# A2_Full_Schematic.net
KiCad netlist of a schematic drawn in Altium Designer
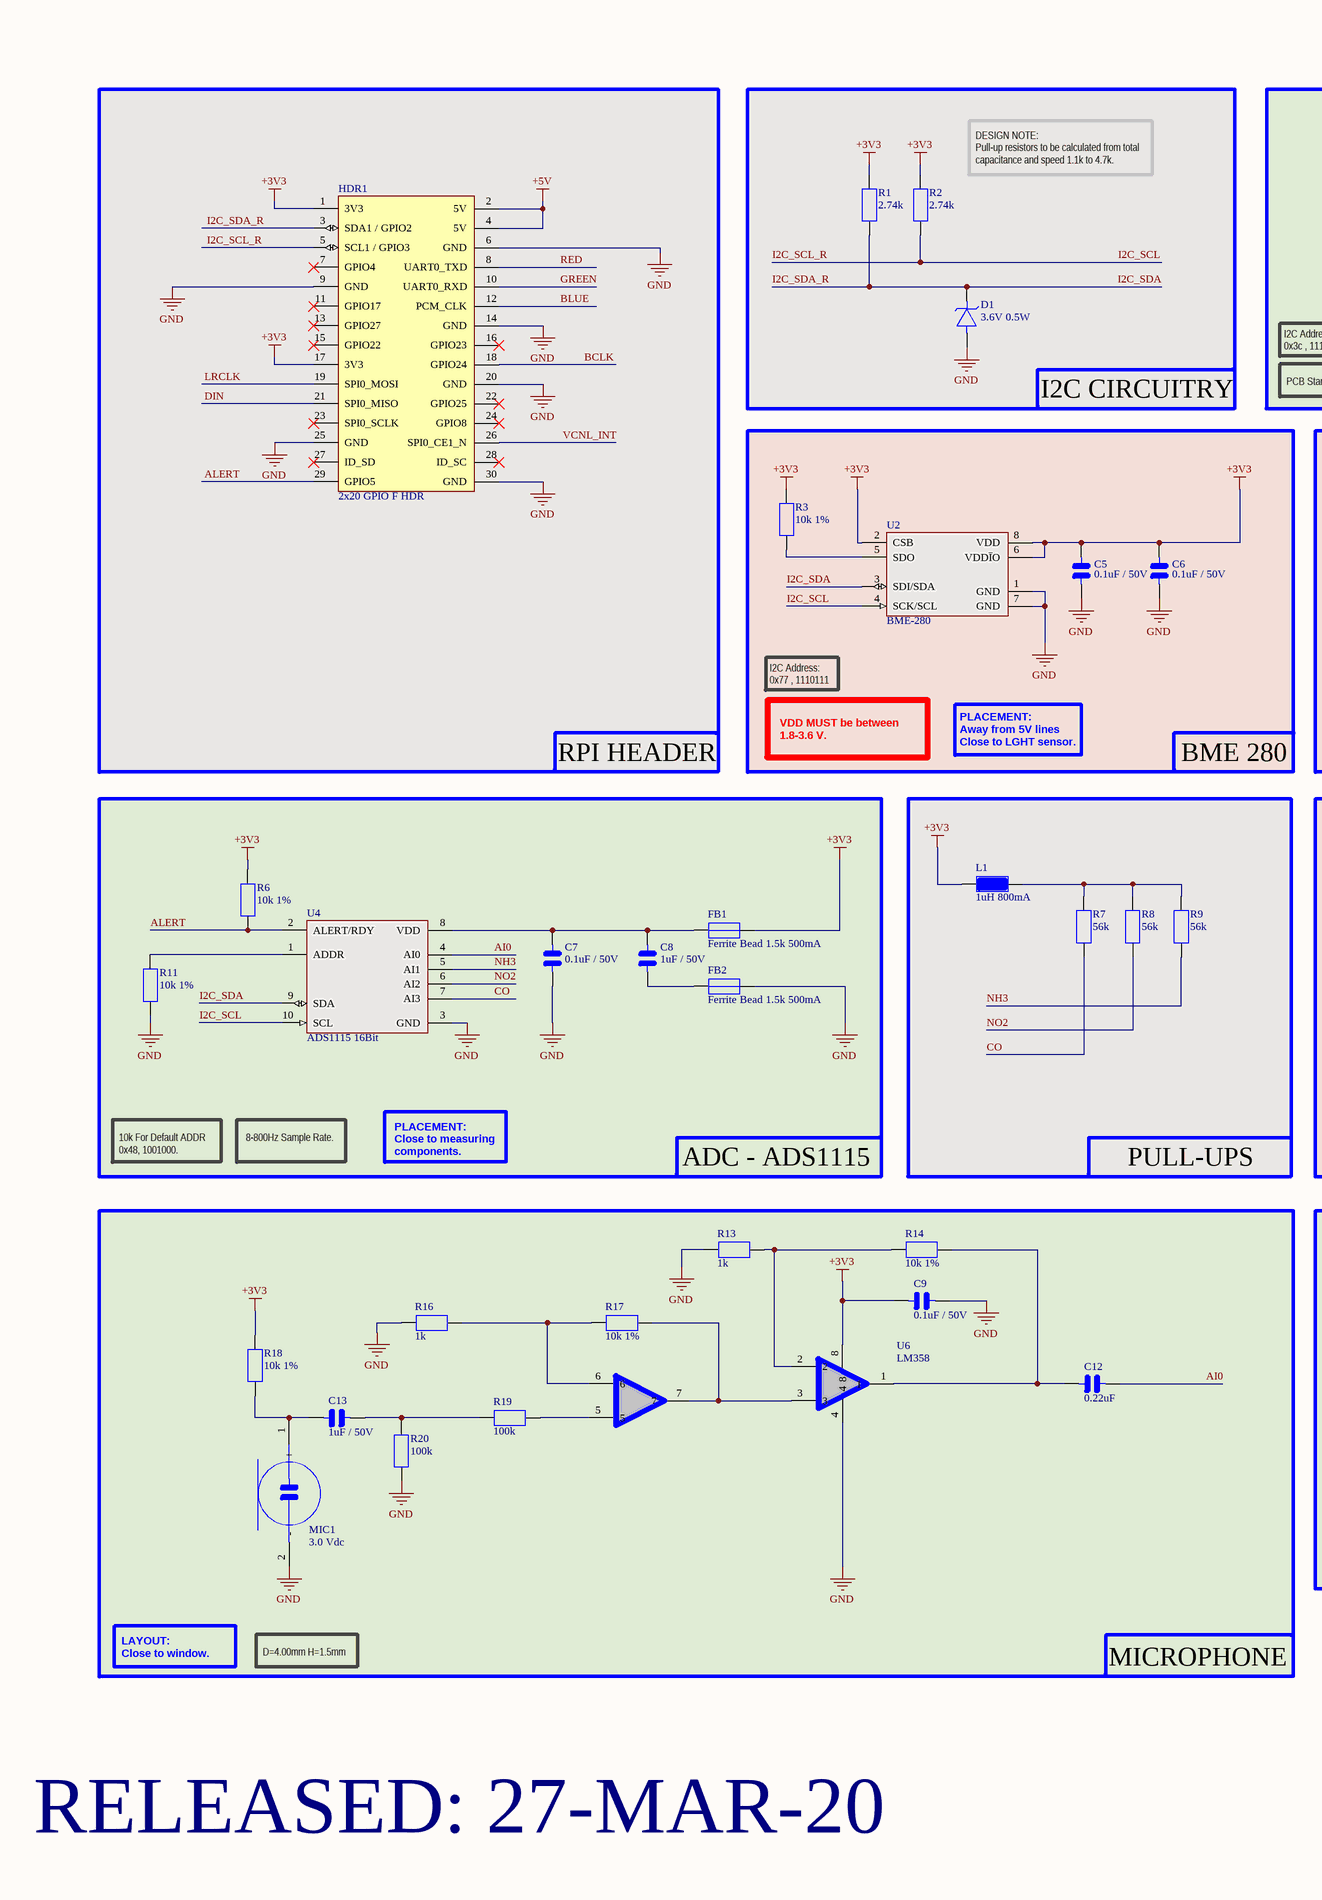
[diagram p0: A2_Full_Schematic.SchDoc, left]
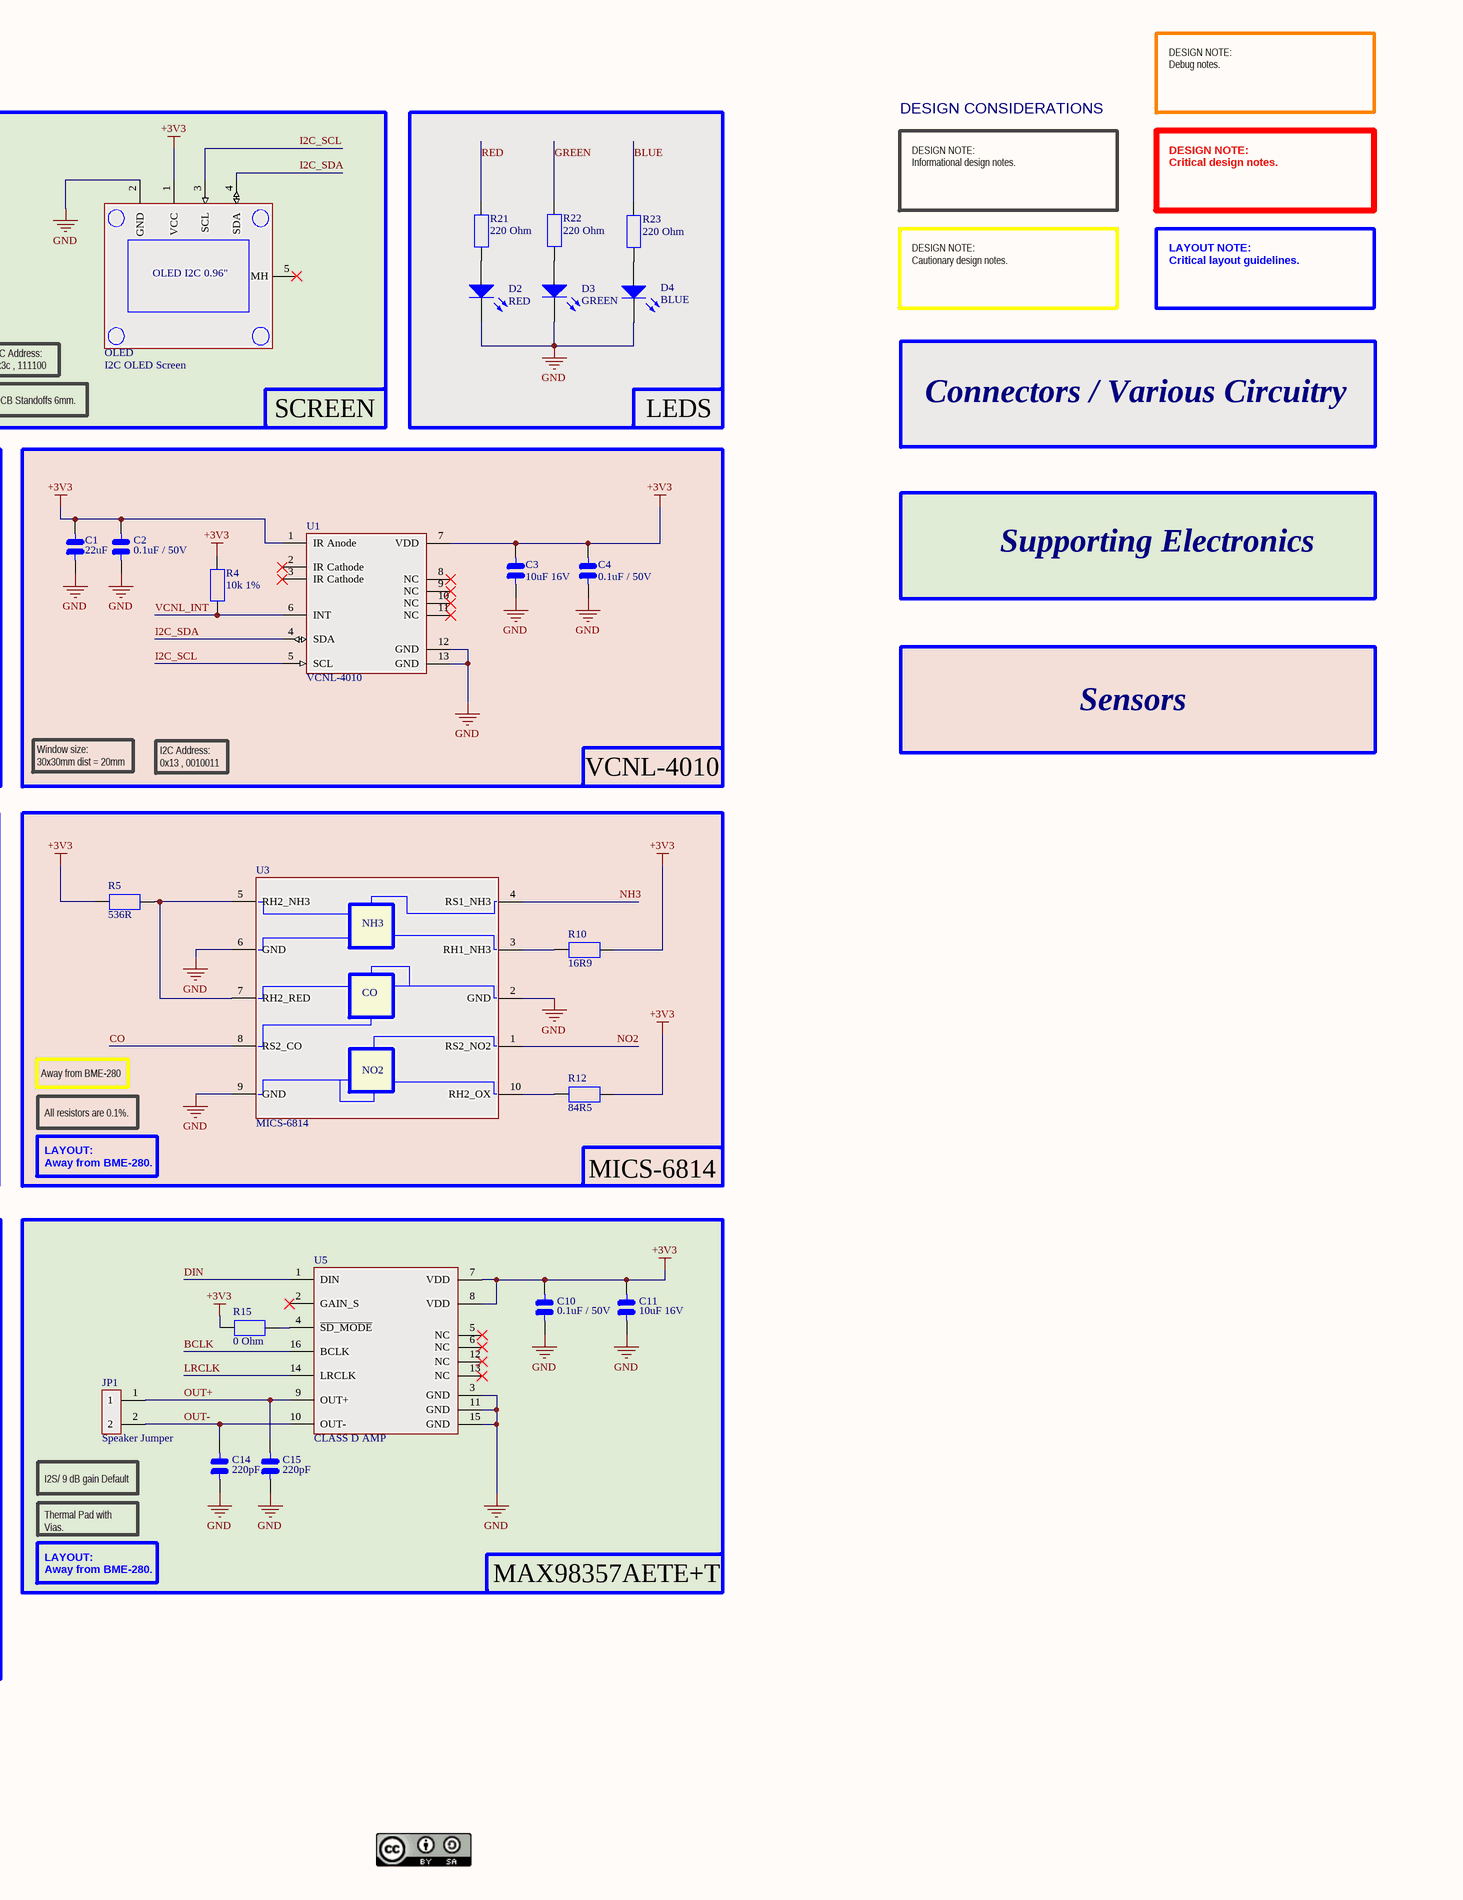
[diagram p1: A2_Full_Schematic.SchDoc, right]

(export (version "E")
  (design (tool "Eeschema 10.0.6"))
  (components
    (comp (ref "C1")
      (value "22uF")
      (footprint "C0805")
      (description "CAP CER 22UF 10V JB 0805")
      (fields (field (name "TOLERANCE") "20%"))
      (libsource (lib "Parts_Lib_SMAQ") (part "C2012JB1A226M085AC"))
    )
    (comp (ref "C2")
      (value "0.1uF / 50V")
      (footprint "C0805")
      (description "CAP CER 0.1UF 50V X7R 0805")
      (fields (field (name "TOLERANCE") "5%"))
      (libsource (lib "Parts_Lib_SMAQ") (part "08055C104JAT4A"))
    )
    (comp (ref "C3")
      (value "10uF 16V")
      (footprint "C0805")
      (libsource (lib "Parts_Lib_SMAQ") (part "0805YC106MAT2A"))
    )
    (comp (ref "C4")
      (value "0.1uF / 50V")
      (footprint "C0805")
      (description "CAP CER 0.1UF 50V X7R 0805")
      (fields (field (name "TOLERANCE") "5%"))
      (libsource (lib "") (part "08055C104JAT4A_2"))
    )
    (comp (ref "C5")
      (value "0.1uF / 50V")
      (footprint "C0805")
      (description "CAP CER 0.1UF 50V X7R 0805")
      (fields (field (name "TOLERANCE") "5%"))
      (libsource (lib "") (part "08055C104JAT4A_1"))
    )
    (comp (ref "C6")
      (value "0.1uF / 50V")
      (footprint "C0805")
      (description "CAP CER 0.1UF 50V X7R 0805")
      (fields (field (name "TOLERANCE") "5%"))
      (libsource (lib "") (part "08055C104JAT4A_1"))
    )
    (comp (ref "C7")
      (value "0.1uF / 50V")
      (footprint "C0805")
      (description "CAP CER 0.1UF 50V X7R 0805")
      (fields (field (name "TOLERANCE") "5%"))
      (libsource (lib "") (part "08055C104JAT4A_1"))
    )
    (comp (ref "C8")
      (value "1uF / 50V")
      (footprint "C0805")
      (fields (field (name "TOLERANCE") "5%") (field (name "VOLTAGE") "50V"))
      (libsource (lib "Parts_Lib_SMAQ") (part "08055C105JAT2A"))
    )
    (comp (ref "C9")
      (value "0.1uF / 50V")
      (footprint "C0805")
      (description "CAP CER 0.1UF 50V X7R 0805")
      (fields (field (name "TOLERANCE") "5%"))
      (libsource (lib "") (part "08055C104JAT4A_3"))
    )
    (comp (ref "C10")
      (value "0.1uF / 50V")
      (footprint "C0805")
      (description "CAP CER 0.1UF 50V X7R 0805")
      (fields (field (name "TOLERANCE") "5%"))
      (libsource (lib "Parts_Lib_SMAQ") (part "08055C104JAT4A"))
    )
    (comp (ref "C11")
      (value "10uF 16V")
      (footprint "C0805")
      (libsource (lib "Parts_Lib_SMAQ") (part "0805YC106MAT2A"))
    )
    (comp (ref "C12")
      (value "0.22uF")
      (footprint "C0805")
      (description "Multilayer Ceramic Capacitors MLCC - SMD/SMT 25V 0.22uF X7R 0805 5% AEC-Q200")
      (libsource (lib "Parts_Lib_SMAQ") (part "08053C224J4Z2A"))
    )
    (comp (ref "C13")
      (value "1uF / 50V")
      (footprint "C0805")
      (fields (field (name "TOLERANCE") "5%") (field (name "VOLTAGE") "50V"))
      (libsource (lib "") (part "08055C105JAT2A_1"))
    )
    (comp (ref "C14")
      (value "220pF")
      (footprint "C0805")
      (description "T&R / COMMERCIAL CHIP")
      (fields (field (name "TOLERANCE") "1%"))
      (libsource (lib "Parts_Lib_SMAQ") (part "08055A221F4T2A"))
    )
    (comp (ref "C15")
      (value "220pF")
      (footprint "C0805")
      (description "T&R / COMMERCIAL CHIP")
      (fields (field (name "TOLERANCE") "1%"))
      (libsource (lib "Parts_Lib_SMAQ") (part "08055A221F4T2A"))
    )
    (comp (ref "D1")
      (value "3.6V 0.5W")
      (footprint "SOD-123")
      (description "Diode Zener Single 3.6V 2% 500mW 2-Pin SOD-123 T/R")
      (fields (field (name "TOLERANCE") "2%"))
      (libsource (lib "Parts_Lib_SMAQ") (part "BZT52B3V6-E3-08"))
    )
    (comp (ref "D2")
      (value "RED")
      (footprint "LED-1")
      (description "Typical RED GaAs LED")
      (fields (field (name "PUBLISHER") "Altium Limited"))
      (libsource (lib "Miscellaneous Devices") (part "LED1"))
    )
    (comp (ref "D3")
      (value "GREEN")
      (footprint "LED-1")
      (description "Typical RED GaAs LED")
      (fields (field (name "PUBLISHER") "Altium Limited"))
      (libsource (lib "Miscellaneous Devices") (part "LED1"))
    )
    (comp (ref "D4")
      (value "BLUE")
      (footprint "LED-1")
      (description "Typical RED GaAs LED")
      (fields (field (name "PUBLISHER") "Altium Limited"))
      (libsource (lib "Miscellaneous Devices") (part "LED1"))
    )
    (comp (ref "FB1")
      (value "Ferrite Bead 1.5k 500mA")
      (footprint "C0805")
      (description "Ferrite Beads Multi-Layer 1.5KOhm 25% 100MHz 500mA 400mOhm DCR 0805")
      (fields (field (name "TOLERANCE") "25%"))
      (libsource (lib "Parts_Lib_SMAQ") (part "MMZ2012Y152B"))
    )
    (comp (ref "FB2")
      (value "Ferrite Bead 1.5k 500mA")
      (footprint "C0805")
      (description "Ferrite Beads Multi-Layer 1.5KOhm 25% 100MHz 500mA 400mOhm DCR 0805")
      (fields (field (name "TOLERANCE") "25%"))
      (libsource (lib "Parts_Lib_SMAQ") (part "MMZ2012Y152B"))
    )
    (comp (ref "HDR1")
      (value "2x20 GPIO F HDR")
      (footprint "2x20_Pi_Header")
      (description "GPIO FEMALE HEADER RASPBERRY PI")
      (libsource (lib "Parts_Lib_SMAQ") (part "2X20 Female Header"))
    )
    (comp (ref "JP1")
      (value "Speaker Jumper")
      (footprint "Speaker Jumper")
      (libsource (lib "Parts_Lib_SMAQ") (part "Speaker Jumper"))
    )
    (comp (ref "L1")
      (value "1uH 800mA")
      (footprint "C0805")
      (description "FIXED IND 1UH 800MA 130 MOHM SMD")
      (libsource (lib "Parts_Lib_SMAQ") (part "KLZ2012MHR1R0HTD25"))
    )
    (comp (ref "MIC1")
      (value "3.0 Vdc")
      (footprint "Speaker Jumper")
      (description "4.0 mm, Omnidirectional, Wire Leads, 3.0 Vdc, IP65 Rated, Electret Condenser Microphone")
      (libsource (lib "Parts_Lib_SMAQ") (part "CMC-4015-25L100"))
    )
    (comp (ref "OLED")
      (value "I2C OLED Screen")
      (footprint "OLED_I2C_0.96\"")
      (libsource (lib "Parts_Lib_SMAQ") (part "OLED_I2C_BREAKOUT"))
    )
    (comp (ref "R1")
      (value "2.74k")
      (footprint "R0805 (2012M)")
      (description "Surface Mount Chip Resistor, Thin Film, AEC-Q200 ERA Series, 2.74 kohm, 125 mW, 0.1%, 100 V")
      (fields (field (name "TOLERANCE") "0.1%"))
      (libsource (lib "Parts_Lib_SMAQ") (part "ERA-6AEB2741V"))
    )
    (comp (ref "R2")
      (value "2.74k")
      (footprint "R0805 (2012M)")
      (description "Surface Mount Chip Resistor, Thin Film, AEC-Q200 ERA Series, 2.74 kohm, 125 mW, 0.1%, 100 V")
      (fields (field (name "TOLERANCE") "0.1%"))
      (libsource (lib "Parts_Lib_SMAQ") (part "ERA-6AEB2741V"))
    )
    (comp (ref "R3")
      (value "10k 1%")
      (footprint "R0805 (2012M)")
      (description "RES SMD 10K OHM 1% 1/8W 0805")
      (fields (field (name "TOLERANCE") "1%"))
      (libsource (lib "Parts_Lib_SMAQ") (part "AT0805FRE0710KL"))
    )
    (comp (ref "R4")
      (value "10k 1%")
      (footprint "R0805 (2012M)")
      (description "RES SMD 10K OHM 1% 1/8W 0805")
      (fields (field (name "TOLERANCE") "1%"))
      (libsource (lib "Parts_Lib_SMAQ") (part "AT0805FRE0710KL"))
    )
    (comp (ref "R5")
      (value "536R")
      (footprint "R0805 (2012M)")
      (description "RES SMD 536 OHM 0.1% 1/8W 0805")
      (fields (field (name "TOLERANCE") "0.1%"))
      (libsource (lib "Parts_Lib_SMAQ") (part "ERA6AEB5360V"))
    )
    (comp (ref "R6")
      (value "10k 1%")
      (footprint "R0805 (2012M)")
      (description "RES SMD 10K OHM 1% 1/8W 0805")
      (fields (field (name "TOLERANCE") "1%"))
      (libsource (lib "Parts_Lib_SMAQ") (part "AT0805FRE0710KL"))
    )
    (comp (ref "R7")
      (value "56k")
      (footprint "R0805 (2012M)")
      (description "RES SMD 56K OHM 0.1% 1/8W 0805")
      (fields (field (name "TOLERANCE") "0.1%"))
      (libsource (lib "Parts_Lib_SMAQ") (part "ERA-6AEB563V"))
    )
    (comp (ref "R8")
      (value "56k")
      (footprint "R0805 (2012M)")
      (description "RES SMD 56K OHM 0.1% 1/8W 0805")
      (fields (field (name "TOLERANCE") "0.1%"))
      (libsource (lib "Parts_Lib_SMAQ") (part "ERA-6AEB563V"))
    )
    (comp (ref "R9")
      (value "56k")
      (footprint "R0805 (2012M)")
      (description "RES SMD 56K OHM 0.1% 1/8W 0805")
      (fields (field (name "TOLERANCE") "0.1%"))
      (libsource (lib "Parts_Lib_SMAQ") (part "ERA-6AEB563V"))
    )
    (comp (ref "R10")
      (value "16R9")
      (footprint "R0805 (2012M)")
      (description "Res Thick Film 0805 16.9 Ohm 1% 1/4W 300ppm/C Molded SMD Punched Carrier T/R")
      (fields (field (name "TOLERANCE") "1%"))
      (libsource (lib "Parts_Lib_SMAQ") (part "ERJ-P06F17R4V"))
    )
    (comp (ref "R11")
      (value "10k 1%")
      (footprint "R0805 (2012M)")
      (description "RES SMD 10K OHM 1% 1/8W 0805")
      (fields (field (name "TOLERANCE") "1%"))
      (libsource (lib "Parts_Lib_SMAQ") (part "AT0805FRE0710KL"))
    )
    (comp (ref "R12")
      (value "84R5")
      (footprint "R0805 (2012M)")
      (description "RES SMD 84.5 OHM 0.1% 1/8W 0805")
      (fields (field (name "TOLERANCE") "0.1%"))
      (libsource (lib "Parts_Lib_SMAQ") (part "ERA-6AEB84R5V"))
    )
    (comp (ref "R13")
      (value "1k")
      (footprint "R0805 (2012M)")
      (description "Res Thin Film 0805 1K Ohm 0.5% 1/8W ±25ppm/°C Molded SMD SMD Punched Carrier T/R")
      (fields (field (name "TOLERANCE") "0.5%"))
      (libsource (lib "Parts_Lib_SMAQ") (part "ERA-6AED102V"))
    )
    (comp (ref "R14")
      (value "10k 1%")
      (footprint "R0805 (2012M)")
      (description "RES SMD 10K OHM 1% 1/8W 0805")
      (fields (field (name "TOLERANCE") "1%"))
      (libsource (lib "Parts_Lib_SMAQ") (part "AT0805FRE0710KL"))
    )
    (comp (ref "R15")
      (value "0 Ohm")
      (footprint "R0805 (2012M)")
      (description "RES SMD 0 OHM JUMPER 1/8W 0805")
      (fields (field (name "TOLERANCE") "5%"))
      (libsource (lib "Parts_Lib_SMAQ") (part "ERJ-6GEY0R00V"))
    )
    (comp (ref "R16")
      (value "1k")
      (footprint "R0805 (2012M)")
      (description "Res Thin Film 0805 1K Ohm 0.5% 1/8W ±25ppm/°C Molded SMD SMD Punched Carrier T/R")
      (fields (field (name "TOLERANCE") "0.5%"))
      (libsource (lib "Parts_Lib_SMAQ") (part "ERA-6AED102V"))
    )
    (comp (ref "R17")
      (value "10k 1%")
      (footprint "R0805 (2012M)")
      (description "RES SMD 10K OHM 1% 1/8W 0805")
      (fields (field (name "TOLERANCE") "1%"))
      (libsource (lib "Parts_Lib_SMAQ") (part "AT0805FRE0710KL"))
    )
    (comp (ref "R18")
      (value "10k 1%")
      (footprint "R0805 (2012M)")
      (description "RES SMD 10K OHM 1% 1/8W 0805")
      (fields (field (name "TOLERANCE") "1%"))
      (libsource (lib "Parts_Lib_SMAQ") (part "AT0805FRE0710KL"))
    )
    (comp (ref "R19")
      (value "100k")
      (footprint "R0805 (2012M)")
      (description "RES SMD 100K OHM 1% 1/8W 0805")
      (fields (field (name "TOLERANCE") "1%"))
      (libsource (lib "Parts_Lib_SMAQ") (part "ERJ-6ENF1003V"))
    )
    (comp (ref "R20")
      (value "100k")
      (footprint "R0805 (2012M)")
      (description "RES SMD 100K OHM 1% 1/8W 0805")
      (fields (field (name "TOLERANCE") "1%"))
      (libsource (lib "Parts_Lib_SMAQ") (part "ERJ-6ENF1003V"))
    )
    (comp (ref "R21")
      (value "220 Ohm")
      (footprint "R0805 (2012M)")
      (description "RES SMD 0 OHM JUMPER 1/8W 0805")
      (fields (field (name "TOLERANCE") "5%"))
      (libsource (lib "Parts_Lib_SMAQ") (part "ERJ-6GEY0R00V"))
    )
    (comp (ref "R22")
      (value "220 Ohm")
      (footprint "R0805 (2012M)")
      (description "RES SMD 0 OHM JUMPER 1/8W 0805")
      (fields (field (name "TOLERANCE") "5%"))
      (libsource (lib "Parts_Lib_SMAQ") (part "ERJ-6GEY0R00V"))
    )
    (comp (ref "R23")
      (value "220 Ohm")
      (footprint "R0805 (2012M)")
      (description "RES SMD 0 OHM JUMPER 1/8W 0805")
      (fields (field (name "TOLERANCE") "5%"))
      (libsource (lib "Parts_Lib_SMAQ") (part "ERJ-6GEY0R00V"))
    )
    (comp (ref "U1")
      (value "VCNL-4010")
      (footprint "VCNL-4010")
      (description "SENS IR PROXIMITY AMB LT 12LLP")
      (libsource (lib "Parts_Lib_SMAQ") (part "VCNL4010-GS08"))
    )
    (comp (ref "U2")
      (value "BME-280")
      (footprint "LGA_8P_0.65MM")
      (description "Pressure, Temperature and Humidity Sensor Digital Output 1.8V 8-Pin LGA T/R")
      (libsource (lib "Parts_Lib_SMAQ") (part "BME280"))
    )
    (comp (ref "U3")
      (value "MICS-6814")
      (footprint "MICS-10")
      (description "SHUT HEIGHT GAGE(119.5MM)")
      (libsource (lib "Parts_Lib_SMAQ") (part "MICS-6814"))
    )
    (comp (ref "U4")
      (value "ADS1115 16Bit")
      (footprint "VSSOP-10")
      (description "IC ADC 16BIT 860SPS LP 10MSOP")
      (libsource (lib "Parts_Lib_SMAQ") (part "ADS1115IDGSR"))
    )
    (comp (ref "U5")
      (value "CLASS D AMP")
      (footprint "16LTHINQFN")
      (description "IC AUDIO AMP CLASS D 16-TQFN")
      (libsource (lib "Parts_Lib_SMAQ") (part "MAX98357AETE+T"))
    )
    (comp (ref "U6")
      (value "LM358")
      (footprint "SOIC-8")
      (description "IC OPAMP GP 700KHZ 8SOIC")
      (libsource (lib "Parts_Lib_SMAQ") (part "LM358DR"))
    )
  )
  (nets
    (net (code "1") (name "+3V3") (class "Default")
      (node (ref "C1") (pin "2") (pinfunction "2_2") (pintype "passive"))
      (node (ref "C10") (pin "2") (pinfunction "2_2") (pintype "passive"))
      (node (ref "C11") (pin "2") (pinfunction "2_2") (pintype "passive"))
      (node (ref "C2") (pin "2") (pinfunction "2_2") (pintype "passive"))
      (node (ref "C3") (pin "2") (pinfunction "2_2") (pintype "passive"))
      (node (ref "C4") (pin "1") (pinfunction "1_1") (pintype "passive"))
      (node (ref "C5") (pin "2") (pinfunction "2_2") (pintype "passive"))
      (node (ref "C6") (pin "2") (pinfunction "2_2") (pintype "passive"))
      (node (ref "C9") (pin "1") (pinfunction "1_1") (pintype "passive"))
      (node (ref "FB1") (pin "2") (pinfunction "2_2") (pintype "passive"))
      (node (ref "HDR1") (pin "1") (pinfunction "3V3_1") (pintype "passive"))
      (node (ref "HDR1") (pin "17") (pinfunction "3V3_17") (pintype "passive"))
      (node (ref "L1") (pin "1") (pinfunction "1_1") (pintype "passive"))
      (node (ref "OLED") (pin "1") (pinfunction "VCC_1") (pintype "passive"))
      (node (ref "R1") (pin "2") (pinfunction "2_2") (pintype "passive"))
      (node (ref "R10") (pin "2") (pinfunction "2_2") (pintype "passive"))
      (node (ref "R12") (pin "2") (pinfunction "2_2") (pintype "passive"))
      (node (ref "R15") (pin "2") (pinfunction "2_2") (pintype "passive"))
      (node (ref "R18") (pin "2") (pinfunction "2_2") (pintype "passive"))
      (node (ref "R2") (pin "2") (pinfunction "2_2") (pintype "passive"))
      (node (ref "R3") (pin "2") (pinfunction "2_2") (pintype "passive"))
      (node (ref "R4") (pin "2") (pinfunction "2_2") (pintype "passive"))
      (node (ref "R5") (pin "1") (pinfunction "1_1") (pintype "passive"))
      (node (ref "R6") (pin "2") (pinfunction "2_2") (pintype "passive"))
      (node (ref "U1") (pin "1") (pinfunction "IR_Anode_1") (pintype "passive"))
      (node (ref "U1") (pin "7") (pinfunction "VDD_7") (pintype "passive"))
      (node (ref "U2") (pin "2") (pinfunction "CSB_2") (pintype "passive"))
      (node (ref "U2") (pin "6") (pinfunction "VDD~{I}O_6") (pintype "power_in"))
      (node (ref "U2") (pin "8") (pinfunction "VDD_8") (pintype "power_in"))
      (node (ref "U5") (pin "7") (pinfunction "VDD_7") (pintype "passive"))
      (node (ref "U5") (pin "8") (pinfunction "VDD_8") (pintype "passive"))
      (node (ref "U6") (pin "8") (pinfunction "8_8") (pintype "passive"))
    )
    (net (code "2") (name "+5V") (class "Default")
      (node (ref "HDR1") (pin "2") (pinfunction "5V_2") (pintype "passive"))
      (node (ref "HDR1") (pin "4") (pinfunction "5V_4") (pintype "passive"))
    )
    (net (code "3") (name "/AI0") (class "Default")
      (node (ref "C12") (pin "2") (pinfunction "2_2") (pintype "passive"))
      (node (ref "U4") (pin "4") (pinfunction "AI0_4") (pintype "passive"))
    )
    (net (code "4") (name "/ALERT") (class "Default")
      (node (ref "HDR1") (pin "29") (pinfunction "GPIO5_29") (pintype "passive"))
      (node (ref "R6") (pin "1") (pinfunction "1_1") (pintype "passive"))
      (node (ref "U4") (pin "2") (pinfunction "ALERT/RDY_2") (pintype "passive"))
    )
    (net (code "5") (name "/BCLK") (class "Default")
      (node (ref "HDR1") (pin "18") (pinfunction "GPIO24_18") (pintype "passive"))
      (node (ref "U5") (pin "16") (pinfunction "BCLK_16") (pintype "passive"))
    )
    (net (code "6") (name "/BLUE") (class "Default")
      (node (ref "HDR1") (pin "12") (pinfunction "PCM_CLK_12") (pintype "passive"))
      (node (ref "R23") (pin "2") (pinfunction "2_2") (pintype "passive"))
    )
    (net (code "7") (name "/CO") (class "Default")
      (node (ref "R7") (pin "1") (pinfunction "1_1") (pintype "passive"))
      (node (ref "U3") (pin "8") (pinfunction "RS2_CO_8") (pintype "passive"))
      (node (ref "U4") (pin "7") (pinfunction "AI3_7") (pintype "passive"))
    )
    (net (code "8") (name "/DIN") (class "Default")
      (node (ref "HDR1") (pin "21") (pinfunction "SPI0_MISO_21") (pintype "passive"))
      (node (ref "U5") (pin "1") (pinfunction "DIN_1") (pintype "passive"))
    )
    (net (code "9") (name "/GREEN") (class "Default")
      (node (ref "HDR1") (pin "10") (pinfunction "UART0_RXD_10") (pintype "passive"))
      (node (ref "R22") (pin "2") (pinfunction "2_2") (pintype "passive"))
    )
    (net (code "10") (name "/I2C_SCL") (class "Default")
      (node (ref "HDR1") (pin "5") (pinfunction "SCL1_/_GPIO3_5") (pintype "bidirectional"))
      (node (ref "OLED") (pin "3") (pinfunction "SCL_3") (pintype "input"))
      (node (ref "R2") (pin "1") (pinfunction "1_1") (pintype "passive"))
      (node (ref "U1") (pin "5") (pinfunction "SCL_5") (pintype "input"))
      (node (ref "U2") (pin "4") (pinfunction "SCK/SCL_4") (pintype "input"))
      (node (ref "U4") (pin "10") (pinfunction "SCL_10") (pintype "input"))
    )
    (net (code "11") (name "/I2C_SDA") (class "Default")
      (node (ref "D1") (pin "2") (pinfunction "2_2") (pintype "passive"))
      (node (ref "HDR1") (pin "3") (pinfunction "SDA1_/_GPIO2_3") (pintype "bidirectional"))
      (node (ref "OLED") (pin "4") (pinfunction "SDA_4") (pintype "bidirectional"))
      (node (ref "R1") (pin "1") (pinfunction "1_1") (pintype "passive"))
      (node (ref "U1") (pin "4") (pinfunction "SDA_4") (pintype "bidirectional"))
      (node (ref "U2") (pin "3") (pinfunction "SDI/SDA_3") (pintype "bidirectional"))
      (node (ref "U4") (pin "9") (pinfunction "SDA_9") (pintype "bidirectional"))
    )
    (net (code "12") (name "/LRCLK") (class "Default")
      (node (ref "HDR1") (pin "19") (pinfunction "SPI0_MOSI_19") (pintype "passive"))
      (node (ref "U5") (pin "14") (pinfunction "LRCLK_14") (pintype "passive"))
    )
    (net (code "13") (name "/NH3") (class "Default")
      (node (ref "R9") (pin "1") (pinfunction "1_1") (pintype "passive"))
      (node (ref "U3") (pin "4") (pinfunction "RS1_NH3_4") (pintype "passive"))
      (node (ref "U4") (pin "5") (pinfunction "AI1_5") (pintype "passive"))
    )
    (net (code "14") (name "/NO2") (class "Default")
      (node (ref "R8") (pin "1") (pinfunction "1_1") (pintype "passive"))
      (node (ref "U3") (pin "1") (pinfunction "RS2_NO2_1") (pintype "passive"))
      (node (ref "U4") (pin "6") (pinfunction "AI2_6") (pintype "passive"))
    )
    (net (code "15") (name "/OUT+") (class "Default")
      (node (ref "C15") (pin "2") (pinfunction "2_2") (pintype "passive"))
      (node (ref "JP1") (pin "1") (pinfunction "1_1") (pintype "passive"))
      (node (ref "U5") (pin "9") (pinfunction "OUT+_9") (pintype "passive"))
    )
    (net (code "16") (name "/OUT-") (class "Default")
      (node (ref "C14") (pin "2") (pinfunction "2_2") (pintype "passive"))
      (node (ref "JP1") (pin "2") (pinfunction "2_2") (pintype "passive"))
      (node (ref "U5") (pin "10") (pinfunction "OUT-_10") (pintype "passive"))
    )
    (net (code "17") (name "/RED") (class "Default")
      (node (ref "HDR1") (pin "8") (pinfunction "UART0_TXD_8") (pintype "passive"))
      (node (ref "R21") (pin "2") (pinfunction "2_2") (pintype "passive"))
    )
    (net (code "18") (name "/VCNL_INT") (class "Default")
      (node (ref "HDR1") (pin "26") (pinfunction "SPI0_CE1_N_26") (pintype "passive"))
      (node (ref "R4") (pin "1") (pinfunction "1_1") (pintype "passive"))
      (node (ref "U1") (pin "6") (pinfunction "INT_6") (pintype "passive"))
    )
    (net (code "19") (name "GND") (class "Default")
      (node (ref "C1") (pin "1") (pinfunction "1_1") (pintype "passive"))
      (node (ref "C10") (pin "1") (pinfunction "1_1") (pintype "passive"))
      (node (ref "C11") (pin "1") (pinfunction "1_1") (pintype "passive"))
      (node (ref "C14") (pin "1") (pinfunction "1_1") (pintype "passive"))
      (node (ref "C15") (pin "1") (pinfunction "1_1") (pintype "passive"))
      (node (ref "C2") (pin "1") (pinfunction "1_1") (pintype "passive"))
      (node (ref "C3") (pin "1") (pinfunction "1_1") (pintype "passive"))
      (node (ref "C4") (pin "2") (pinfunction "2_2") (pintype "passive"))
      (node (ref "C5") (pin "1") (pinfunction "1_1") (pintype "passive"))
      (node (ref "C6") (pin "1") (pinfunction "1_1") (pintype "passive"))
      (node (ref "C7") (pin "1") (pinfunction "1_1") (pintype "passive"))
      (node (ref "C9") (pin "2") (pinfunction "2_2") (pintype "passive"))
      (node (ref "D1") (pin "1") (pinfunction "1_1") (pintype "passive"))
      (node (ref "D2") (pin "2") (pinfunction "K_2") (pintype "passive"))
      (node (ref "D3") (pin "2") (pinfunction "K_2") (pintype "passive"))
      (node (ref "D4") (pin "2") (pinfunction "K_2") (pintype "passive"))
      (node (ref "FB2") (pin "2") (pinfunction "2_2") (pintype "passive"))
      (node (ref "HDR1") (pin "14") (pinfunction "GND_14") (pintype "passive"))
      (node (ref "HDR1") (pin "20") (pinfunction "GND_20") (pintype "passive"))
      (node (ref "HDR1") (pin "25") (pinfunction "GND_25") (pintype "passive"))
      (node (ref "HDR1") (pin "30") (pinfunction "GND_30") (pintype "passive"))
      (node (ref "HDR1") (pin "6") (pinfunction "GND_6") (pintype "passive"))
      (node (ref "HDR1") (pin "9") (pinfunction "GND_9") (pintype "passive"))
      (node (ref "MIC1") (pin "2") (pinfunction "-_2") (pintype "passive"))
      (node (ref "OLED") (pin "2") (pinfunction "GND_2") (pintype "passive"))
      (node (ref "R11") (pin "1") (pinfunction "1_1") (pintype "passive"))
      (node (ref "R13") (pin "1") (pinfunction "1_1") (pintype "passive"))
      (node (ref "R16") (pin "1") (pinfunction "1_1") (pintype "passive"))
      (node (ref "R20") (pin "1") (pinfunction "1_1") (pintype "passive"))
      (node (ref "U1") (pin "12") (pinfunction "GND_12") (pintype "passive"))
      (node (ref "U1") (pin "13") (pinfunction "GND_13") (pintype "passive"))
      (node (ref "U2") (pin "1") (pinfunction "GND_1") (pintype "power_in"))
      (node (ref "U2") (pin "7") (pinfunction "GND_7") (pintype "power_in"))
      (node (ref "U3") (pin "2") (pinfunction "GND_2") (pintype "passive"))
      (node (ref "U3") (pin "6") (pinfunction "GND_6") (pintype "passive"))
      (node (ref "U3") (pin "9") (pinfunction "GND_9") (pintype "passive"))
      (node (ref "U4") (pin "3") (pinfunction "GND_3") (pintype "passive"))
      (node (ref "U5") (pin "11") (pinfunction "GND_11") (pintype "passive"))
      (node (ref "U5") (pin "15") (pinfunction "GND_15") (pintype "passive"))
      (node (ref "U5") (pin "3") (pinfunction "GND_3") (pintype "passive"))
      (node (ref "U6") (pin "4") (pinfunction "4_4") (pintype "passive"))
    )
    (net (code "20") (name "Net-(C8-Pad1)") (class "Default")
      (node (ref "C8") (pin "1") (pinfunction "1_1") (pintype "passive"))
      (node (ref "FB2") (pin "1") (pinfunction "1_1") (pintype "passive"))
    )
    (net (code "21") (name "Net-(C12-Pad1)") (class "Default")
      (node (ref "C12") (pin "1") (pinfunction "1_1") (pintype "passive"))
      (node (ref "R14") (pin "2") (pinfunction "2_2") (pintype "passive"))
      (node (ref "U6") (pin "1") (pinfunction "1_1") (pintype "passive"))
    )
    (net (code "22") (name "Net-(C13-Pad2)") (class "Default")
      (node (ref "C13") (pin "2") (pinfunction "2_2") (pintype "passive"))
      (node (ref "R19") (pin "2") (pinfunction "2_2") (pintype "passive"))
      (node (ref "R20") (pin "2") (pinfunction "2_2") (pintype "passive"))
    )
    (net (code "23") (name "Net-(D2-A)") (class "Default")
      (node (ref "D2") (pin "1") (pinfunction "A_1") (pintype "passive"))
      (node (ref "R21") (pin "1") (pinfunction "1_1") (pintype "passive"))
    )
    (net (code "24") (name "Net-(D3-A)") (class "Default")
      (node (ref "D3") (pin "1") (pinfunction "A_1") (pintype "passive"))
      (node (ref "R22") (pin "1") (pinfunction "1_1") (pintype "passive"))
    )
    (net (code "25") (name "Net-(D4-A)") (class "Default")
      (node (ref "D4") (pin "1") (pinfunction "A_1") (pintype "passive"))
      (node (ref "R23") (pin "1") (pinfunction "1_1") (pintype "passive"))
    )
    (net (code "26") (name "Net-(L1-Pad2)") (class "Default")
      (node (ref "L1") (pin "2") (pinfunction "2_2") (pintype "passive"))
      (node (ref "R7") (pin "2") (pinfunction "2_2") (pintype "passive"))
      (node (ref "R8") (pin "2") (pinfunction "2_2") (pintype "passive"))
      (node (ref "R9") (pin "2") (pinfunction "2_2") (pintype "passive"))
    )
    (net (code "27") (name "Net-(MIC1-+)") (class "Default")
      (node (ref "C13") (pin "1") (pinfunction "1_1") (pintype "passive"))
      (node (ref "MIC1") (pin "1") (pinfunction "+_1") (pintype "passive"))
      (node (ref "R18") (pin "1") (pinfunction "1_1") (pintype "passive"))
    )
    (net (code "28") (name "Net-(R13-Pad2)") (class "Default")
      (node (ref "R13") (pin "2") (pinfunction "2_2") (pintype "passive"))
      (node (ref "R14") (pin "1") (pinfunction "1_1") (pintype "passive"))
      (node (ref "U6") (pin "2") (pinfunction "2_2") (pintype "passive"))
    )
    (net (code "29") (name "Net-(R16-Pad2)") (class "Default")
      (node (ref "R16") (pin "2") (pinfunction "2_2") (pintype "passive"))
      (node (ref "R17") (pin "2") (pinfunction "2_2") (pintype "passive"))
      (node (ref "U6") (pin "6") (pinfunction "6_6") (pintype "passive"))
    )
    (net (code "30") (name "Net-(R17-Pad1)") (class "Default")
      (node (ref "R17") (pin "1") (pinfunction "1_1") (pintype "passive"))
      (node (ref "U6") (pin "3") (pinfunction "3_3") (pintype "passive"))
      (node (ref "U6") (pin "7") (pinfunction "7_7") (pintype "passive"))
    )
    (net (code "31") (name "Net-(R19-Pad1)") (class "Default")
      (node (ref "R19") (pin "1") (pinfunction "1_1") (pintype "passive"))
      (node (ref "U6") (pin "5") (pinfunction "5_5") (pintype "passive"))
    )
    (net (code "32") (name "Net-(U2-SDO)") (class "Default")
      (node (ref "R3") (pin "1") (pinfunction "1_1") (pintype "passive"))
      (node (ref "U2") (pin "5") (pinfunction "SDO_5") (pintype "passive"))
    )
    (net (code "33") (name "Net-(U3-RH1_NH3)") (class "Default")
      (node (ref "R10") (pin "1") (pinfunction "1_1") (pintype "passive"))
      (node (ref "U3") (pin "3") (pinfunction "RH1_NH3_3") (pintype "passive"))
    )
    (net (code "34") (name "Net-(U3-RH2_NH3)") (class "Default")
      (node (ref "R5") (pin "2") (pinfunction "2_2") (pintype "passive"))
      (node (ref "U3") (pin "5") (pinfunction "RH2_NH3_5") (pintype "passive"))
      (node (ref "U3") (pin "7") (pinfunction "RH2_RED_7") (pintype "passive"))
    )
    (net (code "35") (name "Net-(U3-RH2_OX)") (class "Default")
      (node (ref "R12") (pin "1") (pinfunction "1_1") (pintype "passive"))
      (node (ref "U3") (pin "10") (pinfunction "RH2_OX_10") (pintype "passive"))
    )
    (net (code "36") (name "Net-(U4-ADDR)") (class "Default")
      (node (ref "R11") (pin "2") (pinfunction "2_2") (pintype "passive"))
      (node (ref "U4") (pin "1") (pinfunction "ADDR_1") (pintype "passive"))
    )
    (net (code "37") (name "Net-(U4-VDD)") (class "Default")
      (node (ref "C7") (pin "2") (pinfunction "2_2") (pintype "passive"))
      (node (ref "C8") (pin "2") (pinfunction "2_2") (pintype "passive"))
      (node (ref "FB1") (pin "1") (pinfunction "1_1") (pintype "passive"))
      (node (ref "U4") (pin "8") (pinfunction "VDD_8") (pintype "passive"))
    )
    (net (code "38") (name "Net-(U5-~{SD_MODE})") (class "Default")
      (node (ref "R15") (pin "1") (pinfunction "1_1") (pintype "passive"))
      (node (ref "U5") (pin "4") (pinfunction "~{SD_MODE}_4") (pintype "passive"))
    )
    (net (code "39") (name "unconnected-(HDR1-GPIO4-Pad7)") (class "Default")
      (node (ref "HDR1") (pin "7") (pinfunction "GPIO4_7") (pintype "passive+no_connect"))
    )
    (net (code "40") (name "unconnected-(HDR1-GPIO8-Pad24)") (class "Default")
      (node (ref "HDR1") (pin "24") (pinfunction "GPIO8_24") (pintype "passive+no_connect"))
    )
    (net (code "41") (name "unconnected-(HDR1-GPIO17-Pad11)") (class "Default")
      (node (ref "HDR1") (pin "11") (pinfunction "GPIO17_11") (pintype "passive+no_connect"))
    )
    (net (code "42") (name "unconnected-(HDR1-GPIO22-Pad15)") (class "Default")
      (node (ref "HDR1") (pin "15") (pinfunction "GPIO22_15") (pintype "passive+no_connect"))
    )
    (net (code "43") (name "unconnected-(HDR1-GPIO23-Pad16)") (class "Default")
      (node (ref "HDR1") (pin "16") (pinfunction "GPIO23_16") (pintype "passive+no_connect"))
    )
    (net (code "44") (name "unconnected-(HDR1-GPIO25-Pad22)") (class "Default")
      (node (ref "HDR1") (pin "22") (pinfunction "GPIO25_22") (pintype "passive+no_connect"))
    )
    (net (code "45") (name "unconnected-(HDR1-GPIO27-Pad13)") (class "Default")
      (node (ref "HDR1") (pin "13") (pinfunction "GPIO27_13") (pintype "passive+no_connect"))
    )
    (net (code "46") (name "unconnected-(HDR1-ID_SC-Pad28)") (class "Default")
      (node (ref "HDR1") (pin "28") (pinfunction "ID_SC_28") (pintype "passive+no_connect"))
    )
    (net (code "47") (name "unconnected-(HDR1-ID_SD-Pad27)") (class "Default")
      (node (ref "HDR1") (pin "27") (pinfunction "ID_SD_27") (pintype "passive+no_connect"))
    )
    (net (code "48") (name "unconnected-(HDR1-SPI0_SCLK-Pad23)") (class "Default")
      (node (ref "HDR1") (pin "23") (pinfunction "SPI0_SCLK_23") (pintype "passive+no_connect"))
    )
    (net (code "49") (name "unconnected-(OLED-MH-Pad5)") (class "Default")
      (node (ref "OLED") (pin "5") (pinfunction "MH_5") (pintype "passive+no_connect"))
    )
    (net (code "50") (name "unconnected-(U1-IR_Cathode-Pad2)") (class "Default")
      (node (ref "U1") (pin "2") (pinfunction "IR_Cathode_2") (pintype "passive+no_connect"))
    )
    (net (code "51") (name "unconnected-(U1-IR_Cathode-Pad3)") (class "Default")
      (node (ref "U1") (pin "3") (pinfunction "IR_Cathode_3") (pintype "passive+no_connect"))
    )
    (net (code "52") (name "unconnected-(U1-NC-Pad8)") (class "Default")
      (node (ref "U1") (pin "8") (pinfunction "NC_8") (pintype "passive+no_connect"))
    )
    (net (code "53") (name "unconnected-(U1-NC-Pad9)") (class "Default")
      (node (ref "U1") (pin "9") (pinfunction "NC_9") (pintype "passive+no_connect"))
    )
    (net (code "54") (name "unconnected-(U1-NC-Pad10)") (class "Default")
      (node (ref "U1") (pin "10") (pinfunction "NC_10") (pintype "passive+no_connect"))
    )
    (net (code "55") (name "unconnected-(U1-NC-Pad11)") (class "Default")
      (node (ref "U1") (pin "11") (pinfunction "NC_11") (pintype "passive+no_connect"))
    )
    (net (code "56") (name "unconnected-(U5-GAIN_S-Pad2)") (class "Default")
      (node (ref "U5") (pin "2") (pinfunction "GAIN_S_2") (pintype "passive+no_connect"))
    )
    (net (code "57") (name "unconnected-(U5-NC-Pad5)") (class "Default")
      (node (ref "U5") (pin "5") (pinfunction "NC_5") (pintype "passive+no_connect"))
    )
    (net (code "58") (name "unconnected-(U5-NC-Pad6)") (class "Default")
      (node (ref "U5") (pin "6") (pinfunction "NC_6") (pintype "passive+no_connect"))
    )
    (net (code "59") (name "unconnected-(U5-NC-Pad12)") (class "Default")
      (node (ref "U5") (pin "12") (pinfunction "NC_12") (pintype "passive+no_connect"))
    )
    (net (code "60") (name "unconnected-(U5-NC-Pad13)") (class "Default")
      (node (ref "U5") (pin "13") (pinfunction "NC_13") (pintype "passive+no_connect"))
    )
  )
)
